# MGTAVCC.net
KiCad netlist of a schematic drawn in Altium Designer
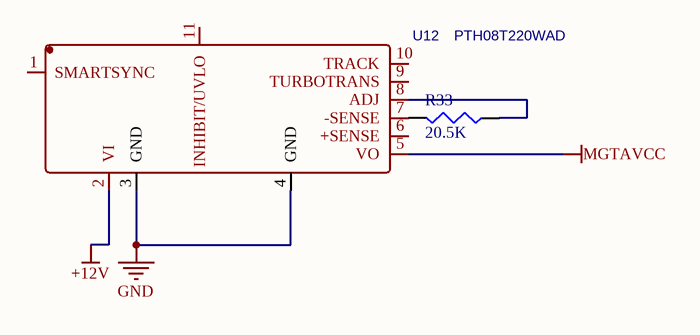
[diagram p0: MGTAVCC.SchDoc]

(export (version "E")
  (design (tool "Eeschema 10.0.6"))
  (components
    (comp (ref "R33")
      (value "20.5K")
      (footprint "J1-0603")
      (description "Resistor")
      (fields (field (name "Comment") "Res3") (field (name "PUBLISHER") "Altium Limited"))
      (libsource (lib "Miscellaneous Devices") (part "Res3"))
    )
    (comp (ref "U12")
      (value "PTH08T220WAD")
      (footprint "PWRM-TH_11P-L23.1-W19.9-P3.17")
      (fields (field (name "BOM_SUPPLIER PART") "C79289") (field (name "CONTRIBUTOR") "LCSC"))
      (libsource (lib "power_chip") (part "PTH08T220WAD"))
    )
  )
  (nets
    (net (code "1") (name "+12V") (class "Default")
      (node (ref "U12") (pin "2") (pinfunction "VI_2") (pintype "passive"))
    )
    (net (code "2") (name "GND") (class "Default")
      (node (ref "U12") (pin "3") (pinfunction "GND_3") (pintype "passive"))
      (node (ref "U12") (pin "4") (pinfunction "GND_4") (pintype "passive"))
    )
    (net (code "3") (name "MGTAVCC") (class "Default")
      (node (ref "U12") (pin "5") (pinfunction "VO_5") (pintype "passive"))
    )
    (net (code "4") (name "Net-(U12--SENSE)") (class "Default")
      (node (ref "R33") (pin "2") (pinfunction "2_2") (pintype "passive"))
      (node (ref "U12") (pin "7") (pinfunction "-SENSE_7") (pintype "passive"))
    )
    (net (code "5") (name "Net-(U12-ADJ)") (class "Default")
      (node (ref "R33") (pin "1") (pinfunction "1_1") (pintype "passive"))
      (node (ref "U12") (pin "8") (pinfunction "ADJ_8") (pintype "passive"))
    )
    (net (code "6") (name "unconnected-(U12-+SENSE-Pad6)") (class "Default")
      (node (ref "U12") (pin "6") (pinfunction "+SENSE_6") (pintype "passive"))
    )
    (net (code "7") (name "unconnected-(U12-INHIBIT{slash}UVLO-Pad11)") (class "Default")
      (node (ref "U12") (pin "11") (pinfunction "INHIBIT/UVLO_11") (pintype "passive"))
    )
    (net (code "8") (name "unconnected-(U12-SMARTSYNC-Pad1)") (class "Default")
      (node (ref "U12") (pin "1") (pinfunction "SMARTSYNC_1") (pintype "passive"))
    )
    (net (code "9") (name "unconnected-(U12-TRACK-Pad10)") (class "Default")
      (node (ref "U12") (pin "10") (pinfunction "TRACK_10") (pintype "passive"))
    )
    (net (code "10") (name "unconnected-(U12-TURBOTRANS-Pad9)") (class "Default")
      (node (ref "U12") (pin "9") (pinfunction "TURBOTRANS_9") (pintype "passive"))
    )
  )
)
